# gameboyzero-landscape.net
KiCad netlist of a schematic drawn in EAGLE
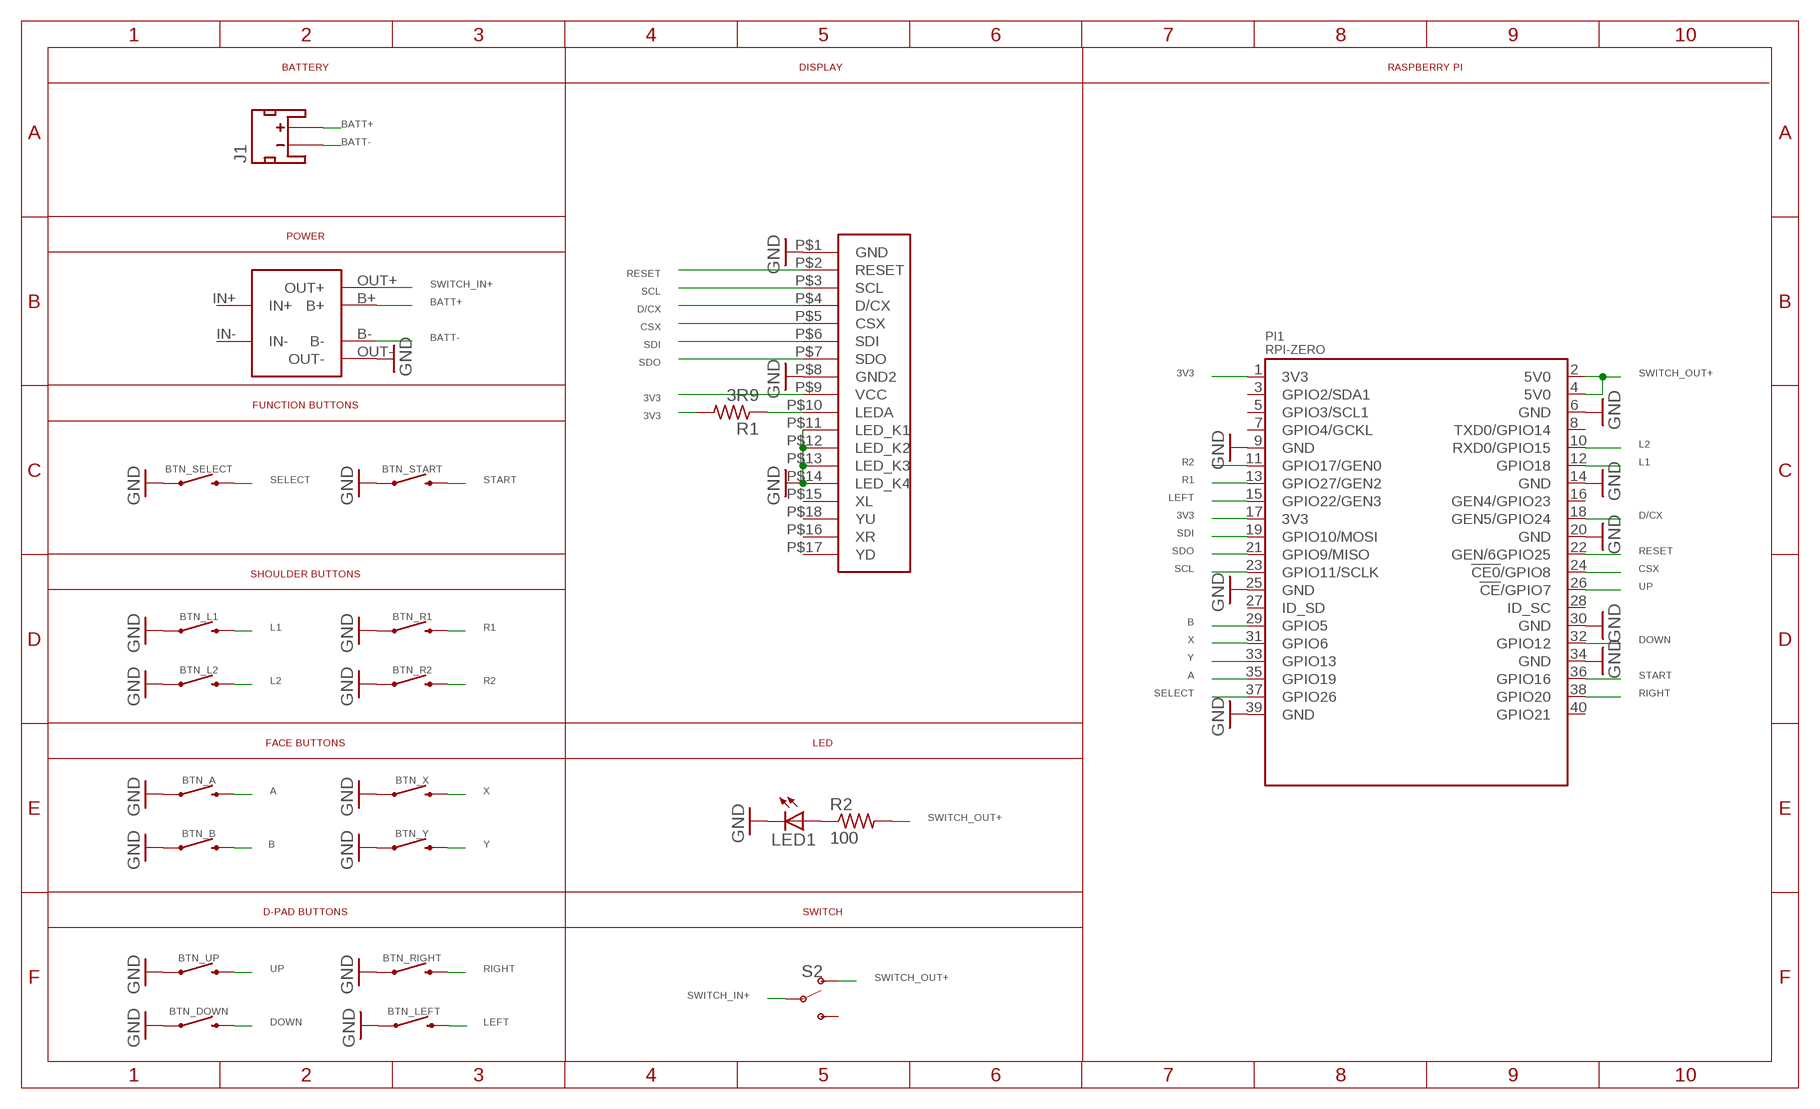
[diagram p0: schematic, sheet 1]

(export (version "E")
  (design (tool "Eeschema 10.0.6"))
  (components
    (comp (ref "BTN_A")
      (value "MOMENTARY-SWITCH-SPST-SMD-12MM")
      (footprint "eagle-import:TACTILE_SWITCH_SMD_12MM")
      (libsource (lib "eagle-import") (part "MOMENTARY-SWITCH-SPST-SMD-12MM"))
    )
    (comp (ref "BTN_B")
      (value "MOMENTARY-SWITCH-SPST-SMD-12MM")
      (footprint "eagle-import:TACTILE_SWITCH_SMD_12MM")
      (libsource (lib "eagle-import") (part "MOMENTARY-SWITCH-SPST-SMD-12MM"))
    )
    (comp (ref "BTN_DOWN")
      (value "MOMENTARY-SWITCH-SPST-SMD-6.2MM-TALL")
      (footprint "eagle-import:TACTILE_SWITCH_SMD_6.2MM_TALL")
      (libsource (lib "eagle-import") (part "MOMENTARY-SWITCH-SPST-SMD-6.2MM-TALL"))
    )
    (comp (ref "BTN_L1")
      (value "MOMENTARY-SWITCH-SPST-SMD-12MM")
      (footprint "eagle-import:TACTILE_SWITCH_SMD_12MM")
      (libsource (lib "eagle-import") (part "MOMENTARY-SWITCH-SPST-SMD-12MM"))
    )
    (comp (ref "BTN_L2")
      (value "MOMENTARY-SWITCH-SPST-SMD-12MM")
      (footprint "eagle-import:TACTILE_SWITCH_SMD_12MM")
      (libsource (lib "eagle-import") (part "MOMENTARY-SWITCH-SPST-SMD-12MM"))
    )
    (comp (ref "BTN_LEFT")
      (value "MOMENTARY-SWITCH-SPST-SMD-6.2MM-TALL")
      (footprint "eagle-import:TACTILE_SWITCH_SMD_6.2MM_TALL")
      (libsource (lib "eagle-import") (part "MOMENTARY-SWITCH-SPST-SMD-6.2MM-TALL"))
    )
    (comp (ref "BTN_R1")
      (value "MOMENTARY-SWITCH-SPST-SMD-12MM")
      (footprint "eagle-import:TACTILE_SWITCH_SMD_12MM")
      (libsource (lib "eagle-import") (part "MOMENTARY-SWITCH-SPST-SMD-12MM"))
    )
    (comp (ref "BTN_R2")
      (value "MOMENTARY-SWITCH-SPST-SMD-12MM")
      (footprint "eagle-import:TACTILE_SWITCH_SMD_12MM")
      (libsource (lib "eagle-import") (part "MOMENTARY-SWITCH-SPST-SMD-12MM"))
    )
    (comp (ref "BTN_RIGHT")
      (value "MOMENTARY-SWITCH-SPST-SMD-6.2MM-TALL")
      (footprint "eagle-import:TACTILE_SWITCH_SMD_6.2MM_TALL")
      (libsource (lib "eagle-import") (part "MOMENTARY-SWITCH-SPST-SMD-6.2MM-TALL"))
    )
    (comp (ref "BTN_SELECT")
      (value "MOMENTARY-SWITCH-SPST-SMD-6.0X3.5MM")
      (footprint "eagle-import:TACTILE_SWITCH_SMD_6.0X3.5MM")
      (libsource (lib "eagle-import") (part "MOMENTARY-SWITCH-SPST-SMD-6.0X3.5MM"))
    )
    (comp (ref "BTN_START")
      (value "MOMENTARY-SWITCH-SPST-SMD-6.0X3.5MM")
      (footprint "eagle-import:TACTILE_SWITCH_SMD_6.0X3.5MM")
      (libsource (lib "eagle-import") (part "MOMENTARY-SWITCH-SPST-SMD-6.0X3.5MM"))
    )
    (comp (ref "BTN_UP")
      (value "MOMENTARY-SWITCH-SPST-SMD-6.2MM-TALL")
      (footprint "eagle-import:TACTILE_SWITCH_SMD_6.2MM_TALL")
      (libsource (lib "eagle-import") (part "MOMENTARY-SWITCH-SPST-SMD-6.2MM-TALL"))
    )
    (comp (ref "BTN_X")
      (value "MOMENTARY-SWITCH-SPST-SMD-12MM")
      (footprint "eagle-import:TACTILE_SWITCH_SMD_12MM")
      (libsource (lib "eagle-import") (part "MOMENTARY-SWITCH-SPST-SMD-12MM"))
    )
    (comp (ref "BTN_Y")
      (value "MOMENTARY-SWITCH-SPST-SMD-12MM")
      (footprint "eagle-import:TACTILE_SWITCH_SMD_12MM")
      (libsource (lib "eagle-import") (part "MOMENTARY-SWITCH-SPST-SMD-12MM"))
    )
    (comp (ref "J1")
      (value "JST_2MM_MALE")
      (footprint "eagle-import:JST-2-SMD")
      (libsource (lib "eagle-import") (part "JST_2MM_MALE"))
    )
    (comp (ref "LED1")
      (value "LEDCHIPLED_0805")
      (footprint "eagle-import:CHIPLED_0805")
      (libsource (lib "eagle-import") (part "LEDCHIPLED_0805"))
    )
    (comp (ref "PI1")
      (value "RPI-ZERO")
      (footprint "eagle-import:RASPBERRYPI_BASTELSTUBE_V13_RASPI_BOARD_B+_FULL")
      (libsource (lib "eagle-import") (part "RPI-ZERO"))
    )
    (comp (ref "POWER1")
      (value "03962A")
      (footprint "eagle-import:03962A")
      (libsource (lib "eagle-import") (part "03962A"))
    )
    (comp (ref "R1")
      (value "3R9")
      (footprint "eagle-import:R0805")
      (libsource (lib "eagle-import") (part "R-US_R0805"))
    )
    (comp (ref "R2")
      (value "100")
      (footprint "eagle-import:R0805")
      (libsource (lib "eagle-import") (part "R-US_R0805"))
    )
    (comp (ref "S2")
      (value "SWITCH-SPDT-SMD-RIGHT-ANGLE")
      (footprint "eagle-import:SWITCH_SPST_SMD_A")
      (libsource (lib "eagle-import") (part "SWITCH-SPDT-SMD-RIGHT-ANGLE"))
    )
    (comp (ref "SCREEN1")
      (value "GAMEBOYZEROHANDHELDDISPLAYS-3.2")
      (footprint "eagle-import:GAMEBOYZEROHANDHELDDISPLAYS-3.2")
      (libsource (lib "eagle-import") (part "GAMEBOYZEROHANDHELDDISPLAYS-3.2"))
    )
  )
  (nets
    (net (code "1") (name "/3V3") (class "Default")
      (node (ref "PI1") (pin "1") (pinfunction "3V3_1") (pintype "power_in"))
      (node (ref "PI1") (pin "17") (pinfunction "3V3_17") (pintype "power_in"))
      (node (ref "R1") (pin "2") (pinfunction "2_2") (pintype "passive"))
      (node (ref "SCREEN1") (pin "P$9") (pinfunction "VCC_P$9") (pintype "bidirectional"))
    )
    (net (code "2") (name "/A") (class "Default")
      (node (ref "BTN_A") (pin "3") (pinfunction "2_3") (pintype "passive"))
      (node (ref "PI1") (pin "35") (pinfunction "GPIO19_35") (pintype "bidirectional"))
    )
    (net (code "3") (name "/B") (class "Default")
      (node (ref "BTN_B") (pin "3") (pinfunction "2_3") (pintype "passive"))
      (node (ref "PI1") (pin "29") (pinfunction "GPIO5_29") (pintype "bidirectional"))
    )
    (net (code "4") (name "/BATT+") (class "Default")
      (node (ref "J1") (pin "2") (pinfunction "+_2") (pintype "bidirectional"))
      (node (ref "POWER1") (pin "B+") (pinfunction "B+_B+") (pintype "bidirectional"))
    )
    (net (code "5") (name "/BATT-") (class "Default")
      (node (ref "J1") (pin "1") (pinfunction "-_1") (pintype "bidirectional"))
      (node (ref "POWER1") (pin "B-") (pinfunction "B-_B-") (pintype "bidirectional"))
    )
    (net (code "6") (name "/CSX") (class "Default")
      (node (ref "PI1") (pin "24") (pinfunction "~{CE0}/GPIO8_24") (pintype "bidirectional"))
      (node (ref "SCREEN1") (pin "P$5") (pinfunction "CSX_P$5") (pintype "bidirectional"))
    )
    (net (code "7") (name "/DOWN") (class "Default")
      (node (ref "BTN_DOWN") (pin "B2") (pinfunction "2_B2") (pintype "passive"))
      (node (ref "PI1") (pin "32") (pinfunction "GPIO12_32") (pintype "bidirectional"))
    )
    (net (code "8") (name "/D{slash}CX") (class "Default")
      (node (ref "PI1") (pin "18") (pinfunction "GEN5/GPIO24_18") (pintype "bidirectional"))
      (node (ref "SCREEN1") (pin "P$4") (pinfunction "D/CX_P$4") (pintype "bidirectional"))
    )
    (net (code "9") (name "/L1") (class "Default")
      (node (ref "BTN_L1") (pin "3") (pinfunction "2_3") (pintype "passive"))
      (node (ref "PI1") (pin "12") (pinfunction "GPIO18_12") (pintype "bidirectional"))
    )
    (net (code "10") (name "/L2") (class "Default")
      (node (ref "BTN_L2") (pin "3") (pinfunction "2_3") (pintype "passive"))
      (node (ref "PI1") (pin "10") (pinfunction "RXD0/GPIO15_10") (pintype "bidirectional"))
    )
    (net (code "11") (name "/LEFT") (class "Default")
      (node (ref "BTN_LEFT") (pin "B2") (pinfunction "2_B2") (pintype "passive"))
      (node (ref "PI1") (pin "15") (pinfunction "GPIO22/GEN3_15") (pintype "bidirectional"))
    )
    (net (code "12") (name "/R1") (class "Default")
      (node (ref "BTN_R1") (pin "3") (pinfunction "2_3") (pintype "passive"))
      (node (ref "PI1") (pin "13") (pinfunction "GPIO27/GEN2_13") (pintype "bidirectional"))
    )
    (net (code "13") (name "/R2") (class "Default")
      (node (ref "BTN_R2") (pin "3") (pinfunction "2_3") (pintype "passive"))
      (node (ref "PI1") (pin "11") (pinfunction "GPIO17/GEN0_11") (pintype "bidirectional"))
    )
    (net (code "14") (name "/RESET") (class "Default")
      (node (ref "PI1") (pin "22") (pinfunction "GEN/6GPIO25_22") (pintype "bidirectional"))
      (node (ref "SCREEN1") (pin "P$2") (pinfunction "RESET_P$2") (pintype "bidirectional"))
    )
    (net (code "15") (name "/RIGHT") (class "Default")
      (node (ref "BTN_RIGHT") (pin "B2") (pinfunction "2_B2") (pintype "passive"))
      (node (ref "PI1") (pin "38") (pinfunction "GPIO20_38") (pintype "bidirectional"))
    )
    (net (code "16") (name "/SCL") (class "Default")
      (node (ref "PI1") (pin "23") (pinfunction "GPIO11/SCLK_23") (pintype "bidirectional"))
      (node (ref "SCREEN1") (pin "P$3") (pinfunction "SCL_P$3") (pintype "bidirectional"))
    )
    (net (code "17") (name "/SDI") (class "Default")
      (node (ref "PI1") (pin "19") (pinfunction "GPIO10/MOSI_19") (pintype "bidirectional"))
      (node (ref "SCREEN1") (pin "P$6") (pinfunction "SDI_P$6") (pintype "bidirectional"))
    )
    (net (code "18") (name "/SDO") (class "Default")
      (node (ref "PI1") (pin "21") (pinfunction "GPIO9/MISO_21") (pintype "bidirectional"))
      (node (ref "SCREEN1") (pin "P$7") (pinfunction "SDO_P$7") (pintype "bidirectional"))
    )
    (net (code "19") (name "/SELECT") (class "Default")
      (node (ref "BTN_SELECT") (pin "2") (pinfunction "2_2") (pintype "passive"))
      (node (ref "PI1") (pin "37") (pinfunction "GPIO26_37") (pintype "bidirectional"))
    )
    (net (code "20") (name "/START") (class "Default")
      (node (ref "BTN_START") (pin "2") (pinfunction "2_2") (pintype "passive"))
      (node (ref "PI1") (pin "36") (pinfunction "GPIO16_36") (pintype "bidirectional"))
    )
    (net (code "21") (name "/SWITCH_IN+") (class "Default")
      (node (ref "POWER1") (pin "OUT+") (pinfunction "OUT+_OUT+") (pintype "bidirectional"))
      (node (ref "S2") (pin "2") (pinfunction "P_2") (pintype "passive"))
    )
    (net (code "22") (name "/SWITCH_OUT+") (class "Default")
      (node (ref "PI1") (pin "2") (pinfunction "5V0_2") (pintype "power_in"))
      (node (ref "PI1") (pin "4") (pinfunction "5V0_4") (pintype "power_in"))
      (node (ref "R2") (pin "2") (pinfunction "2_2") (pintype "passive"))
      (node (ref "S2") (pin "1") (pinfunction "O_1") (pintype "passive"))
    )
    (net (code "23") (name "/UP") (class "Default")
      (node (ref "BTN_UP") (pin "B2") (pinfunction "2_B2") (pintype "passive"))
      (node (ref "PI1") (pin "26") (pinfunction "~{CE}/GPIO7_26") (pintype "bidirectional"))
    )
    (net (code "24") (name "/X") (class "Default")
      (node (ref "BTN_X") (pin "3") (pinfunction "2_3") (pintype "passive"))
      (node (ref "PI1") (pin "31") (pinfunction "GPIO6_31") (pintype "bidirectional"))
    )
    (net (code "25") (name "/Y") (class "Default")
      (node (ref "BTN_Y") (pin "3") (pinfunction "2_3") (pintype "passive"))
      (node (ref "PI1") (pin "33") (pinfunction "GPIO13_33") (pintype "bidirectional"))
    )
    (net (code "26") (name "GND") (class "Default")
      (node (ref "BTN_A") (pin "1") (pinfunction "1_1") (pintype "passive"))
      (node (ref "BTN_B") (pin "1") (pinfunction "1_1") (pintype "passive"))
      (node (ref "BTN_DOWN") (pin "A2") (pinfunction "1_A2") (pintype "passive"))
      (node (ref "BTN_L1") (pin "1") (pinfunction "1_1") (pintype "passive"))
      (node (ref "BTN_L2") (pin "1") (pinfunction "1_1") (pintype "passive"))
      (node (ref "BTN_LEFT") (pin "A2") (pinfunction "1_A2") (pintype "passive"))
      (node (ref "BTN_R1") (pin "1") (pinfunction "1_1") (pintype "passive"))
      (node (ref "BTN_R2") (pin "1") (pinfunction "1_1") (pintype "passive"))
      (node (ref "BTN_RIGHT") (pin "A2") (pinfunction "1_A2") (pintype "passive"))
      (node (ref "BTN_SELECT") (pin "1") (pinfunction "1_1") (pintype "passive"))
      (node (ref "BTN_START") (pin "1") (pinfunction "1_1") (pintype "passive"))
      (node (ref "BTN_UP") (pin "A2") (pinfunction "1_A2") (pintype "passive"))
      (node (ref "BTN_X") (pin "1") (pinfunction "1_1") (pintype "passive"))
      (node (ref "BTN_Y") (pin "1") (pinfunction "1_1") (pintype "passive"))
      (node (ref "LED1") (pin "C") (pinfunction "C_C") (pintype "passive"))
      (node (ref "PI1") (pin "14") (pinfunction "GND_14") (pintype "power_in"))
      (node (ref "PI1") (pin "20") (pinfunction "GND_20") (pintype "power_in"))
      (node (ref "PI1") (pin "25") (pinfunction "GND_25") (pintype "power_in"))
      (node (ref "PI1") (pin "30") (pinfunction "GND_30") (pintype "power_in"))
      (node (ref "PI1") (pin "34") (pinfunction "GND_34") (pintype "power_in"))
      (node (ref "PI1") (pin "39") (pinfunction "GND_39") (pintype "power_in"))
      (node (ref "PI1") (pin "6") (pinfunction "GND_6") (pintype "power_in"))
      (node (ref "PI1") (pin "9") (pinfunction "GND_9") (pintype "power_in"))
      (node (ref "POWER1") (pin "OUT-") (pinfunction "OUT-_OUT-") (pintype "bidirectional"))
      (node (ref "SCREEN1") (pin "P$1") (pinfunction "GND_P$1") (pintype "bidirectional"))
      (node (ref "SCREEN1") (pin "P$11") (pinfunction "LED_K1_P$11") (pintype "bidirectional"))
      (node (ref "SCREEN1") (pin "P$12") (pinfunction "LED_K2_P$12") (pintype "bidirectional"))
      (node (ref "SCREEN1") (pin "P$13") (pinfunction "LED_K3_P$13") (pintype "bidirectional"))
      (node (ref "SCREEN1") (pin "P$14") (pinfunction "LED_K4_P$14") (pintype "bidirectional"))
      (node (ref "SCREEN1") (pin "P$8") (pinfunction "GND2_P$8") (pintype "bidirectional"))
    )
    (net (code "27") (name "Net-(LED1-PadA)") (class "Default")
      (node (ref "LED1") (pin "A") (pinfunction "A_A") (pintype "passive"))
      (node (ref "R2") (pin "1") (pinfunction "1_1") (pintype "passive"))
    )
    (net (code "28") (name "Net-(SCREEN1-LEDA)") (class "Default")
      (node (ref "R1") (pin "1") (pinfunction "1_1") (pintype "passive"))
      (node (ref "SCREEN1") (pin "P$10") (pinfunction "LEDA_P$10") (pintype "bidirectional"))
    )
    (net (code "29") (name "unconnected-(J1-PAD1-PadNC1)") (class "Default")
      (node (ref "J1") (pin "NC1") (pinfunction "PAD1_NC1") (pintype "bidirectional"))
    )
    (net (code "30") (name "unconnected-(J1-PAD2-PadNC2)") (class "Default")
      (node (ref "J1") (pin "NC2") (pinfunction "PAD2_NC2") (pintype "bidirectional"))
    )
    (net (code "31") (name "unconnected-(PI1-GEN4{slash}GPIO23-Pad16)") (class "Default")
      (node (ref "PI1") (pin "16") (pinfunction "GEN4/GPIO23_16") (pintype "bidirectional"))
    )
    (net (code "32") (name "unconnected-(PI1-GPIO2{slash}SDA1-Pad3)") (class "Default")
      (node (ref "PI1") (pin "3") (pinfunction "GPIO2/SDA1_3") (pintype "bidirectional"))
    )
    (net (code "33") (name "unconnected-(PI1-GPIO3{slash}SCL1-Pad5)") (class "Default")
      (node (ref "PI1") (pin "5") (pinfunction "GPIO3/SCL1_5") (pintype "bidirectional"))
    )
    (net (code "34") (name "unconnected-(PI1-GPIO4{slash}GCKL-Pad7)") (class "Default")
      (node (ref "PI1") (pin "7") (pinfunction "GPIO4/GCKL_7") (pintype "bidirectional"))
    )
    (net (code "35") (name "unconnected-(PI1-GPIO21-Pad40)") (class "Default")
      (node (ref "PI1") (pin "40") (pinfunction "GPIO21_40") (pintype "bidirectional"))
    )
    (net (code "36") (name "unconnected-(PI1-ID_SC-Pad28)") (class "Default")
      (node (ref "PI1") (pin "28") (pinfunction "ID_SC_28") (pintype "bidirectional"))
    )
    (net (code "37") (name "unconnected-(PI1-ID_SD-Pad27)") (class "Default")
      (node (ref "PI1") (pin "27") (pinfunction "ID_SD_27") (pintype "bidirectional"))
    )
    (net (code "38") (name "unconnected-(PI1-TXD0{slash}GPIO14-Pad8)") (class "Default")
      (node (ref "PI1") (pin "8") (pinfunction "TXD0/GPIO14_8") (pintype "bidirectional"))
    )
    (net (code "39") (name "unconnected-(POWER1-PadIN+)") (class "Default")
      (node (ref "POWER1") (pin "IN+") (pinfunction "IN+_IN+") (pintype "bidirectional"))
    )
    (net (code "40") (name "unconnected-(POWER1-PadIN-)") (class "Default")
      (node (ref "POWER1") (pin "IN-") (pinfunction "IN-_IN-") (pintype "bidirectional"))
    )
    (net (code "41") (name "unconnected-(S2-S-Pad3)") (class "Default")
      (node (ref "S2") (pin "3") (pinfunction "S_3") (pintype "passive"))
    )
    (net (code "42") (name "unconnected-(SCREEN1-XL-PadP$15)") (class "Default")
      (node (ref "SCREEN1") (pin "P$15") (pinfunction "XL_P$15") (pintype "bidirectional"))
    )
    (net (code "43") (name "unconnected-(SCREEN1-XR-PadP$16)") (class "Default")
      (node (ref "SCREEN1") (pin "P$16") (pinfunction "XR_P$16") (pintype "bidirectional"))
    )
    (net (code "44") (name "unconnected-(SCREEN1-YD-PadP$17)") (class "Default")
      (node (ref "SCREEN1") (pin "P$17") (pinfunction "YD_P$17") (pintype "bidirectional"))
    )
    (net (code "45") (name "unconnected-(SCREEN1-YU-PadP$18)") (class "Default")
      (node (ref "SCREEN1") (pin "P$18") (pinfunction "YU_P$18") (pintype "bidirectional"))
    )
  )
)
